# A02_DRV8316.net
KiCad netlist of a schematic drawn in Altium Designer
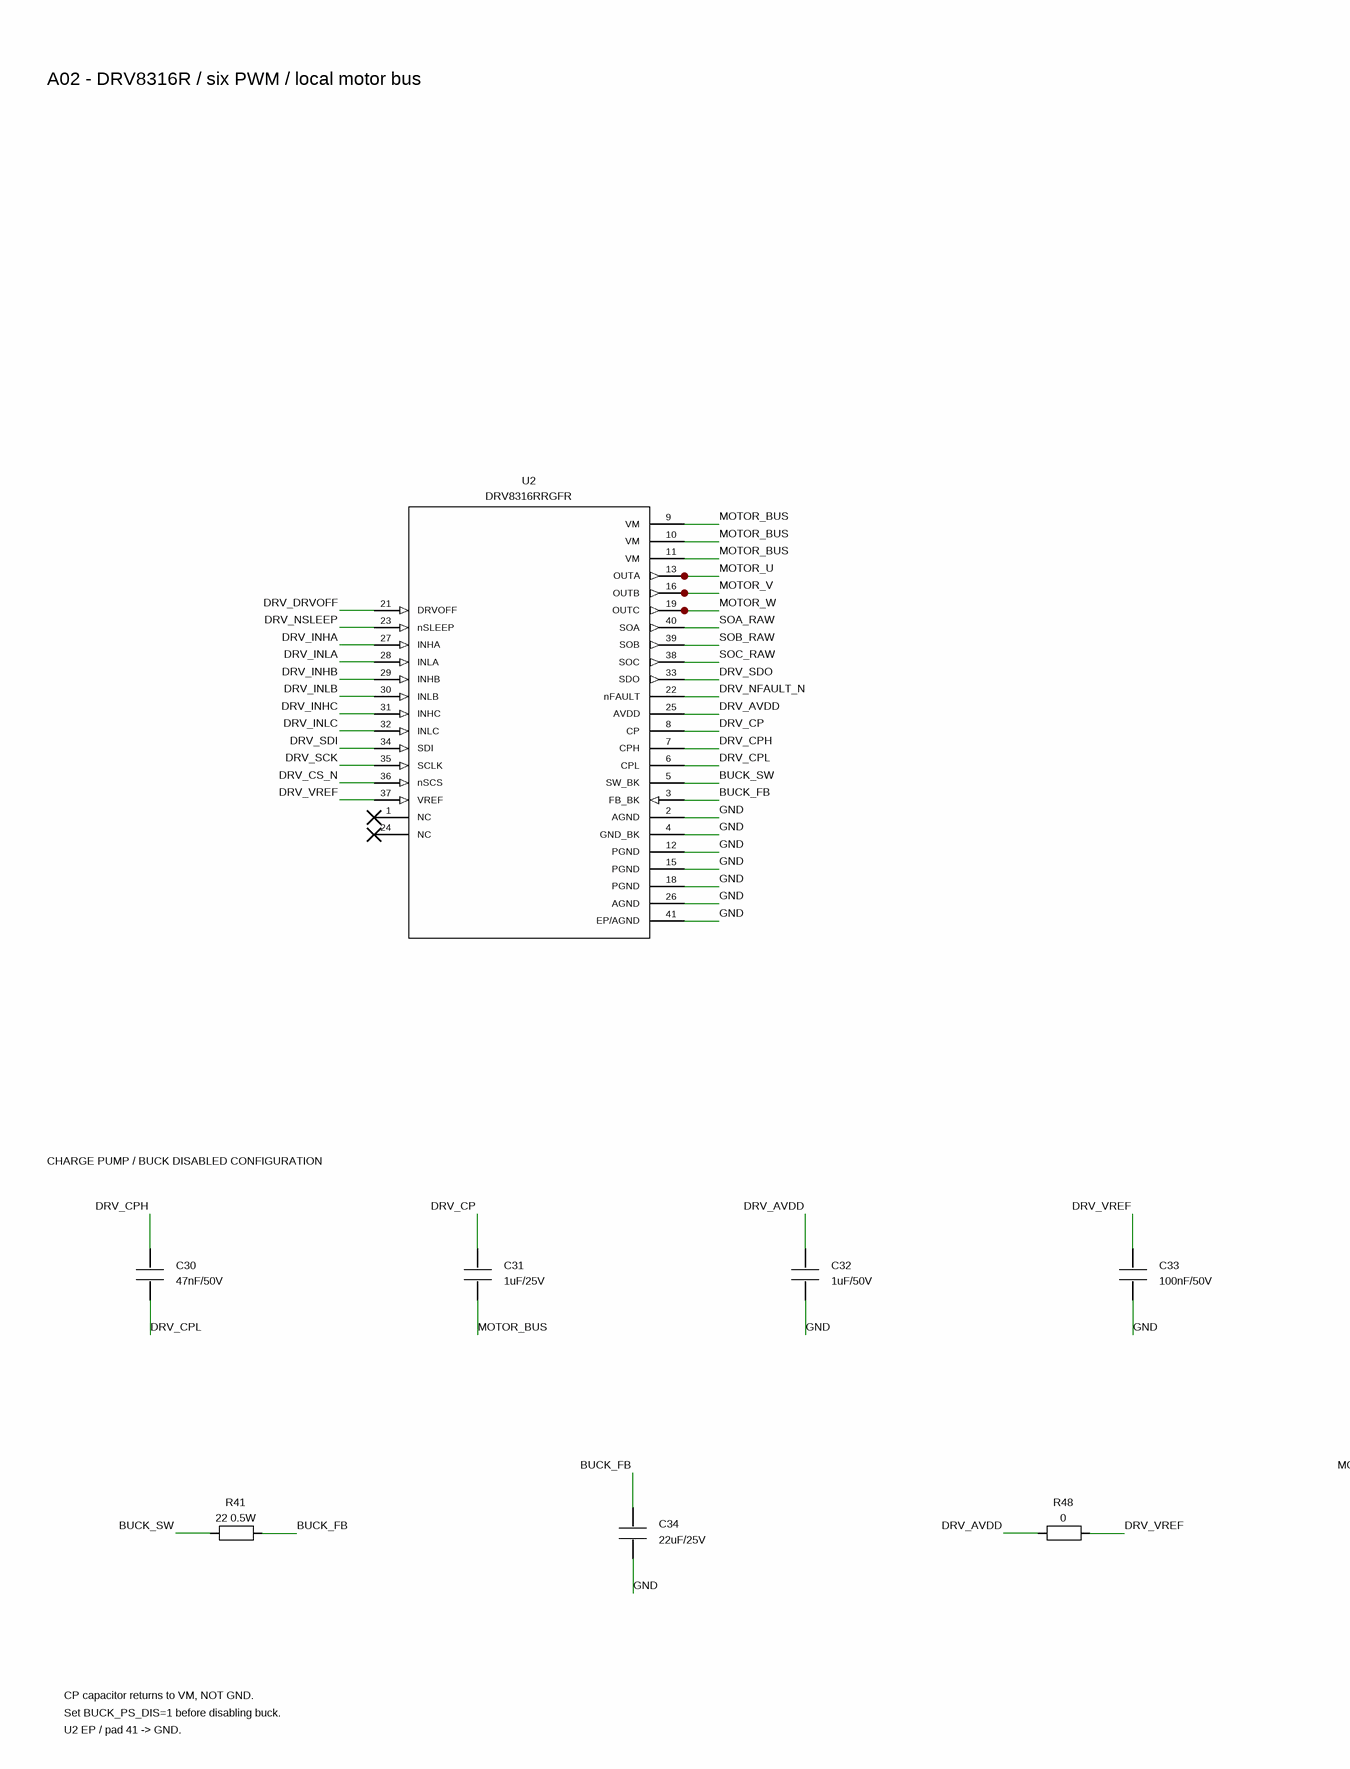
[diagram p0: A02_DRV8316.SchDoc, left]
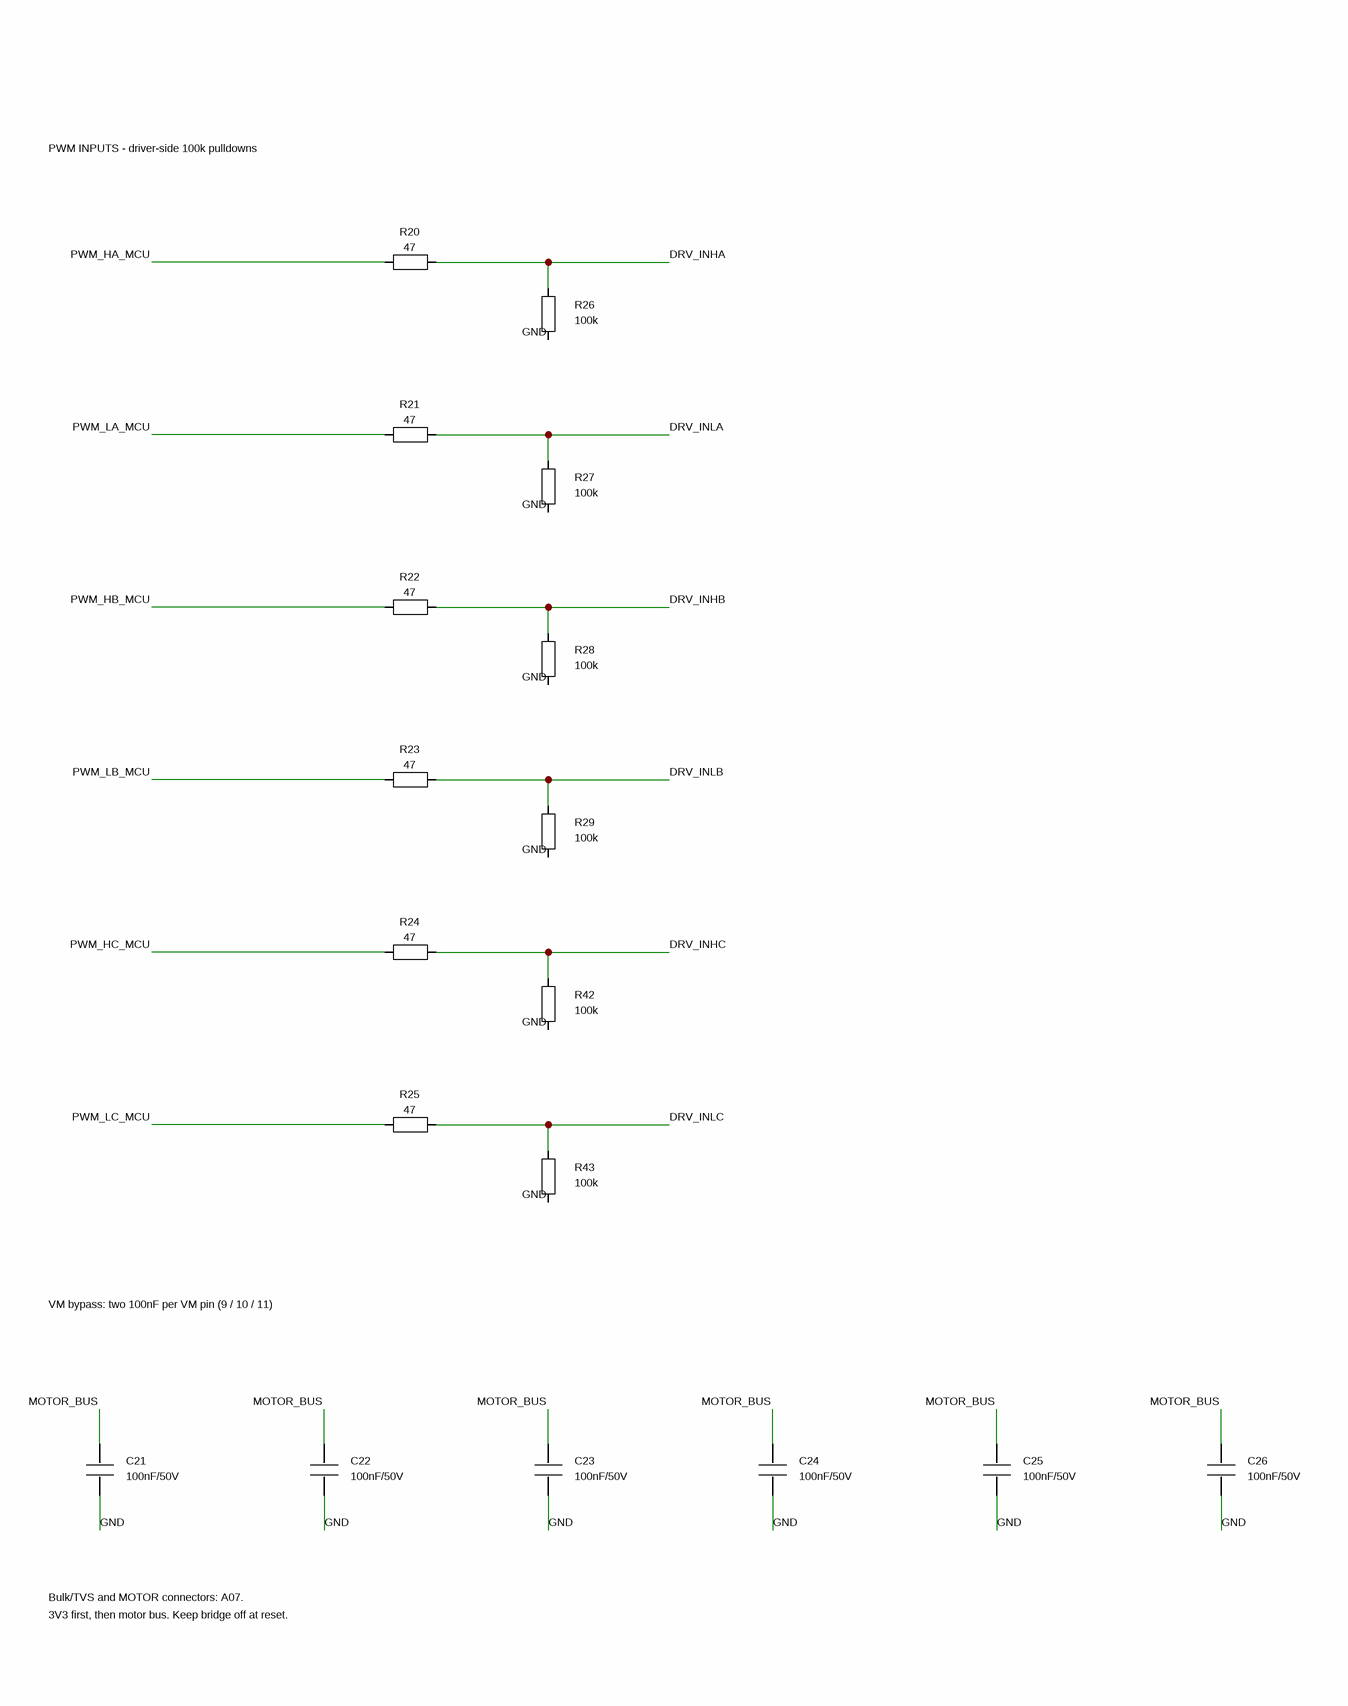
[diagram p1: A02_DRV8316.SchDoc, right]

(export (version "E")
  (design (tool "Eeschema 10.0.6"))
  (components
    (comp (ref "C21")
      (value "100nF/50V")
      (footprint "User_STM32F407_Ctrl:C0603_M")
      (description "电容")
      (fields (field (name "MPN") "CL10B104KB8NNNC"))
      (libsource (lib "altium-import") (part "root_0_C_"))
    )
    (comp (ref "C22")
      (value "100nF/50V")
      (footprint "User_STM32F407_Ctrl:C0603_M")
      (description "电容")
      (fields (field (name "MPN") "CL10B104KB8NNNC"))
      (libsource (lib "altium-import") (part "root_0_C_"))
    )
    (comp (ref "C23")
      (value "100nF/50V")
      (footprint "User_STM32F407_Ctrl:C0603_M")
      (description "电容")
      (fields (field (name "MPN") "CL10B104KB8NNNC"))
      (libsource (lib "altium-import") (part "root_0_C_"))
    )
    (comp (ref "C24")
      (value "100nF/50V")
      (footprint "User_STM32F407_Ctrl:C0603_M")
      (description "电容")
      (fields (field (name "MPN") "CL10B104KB8NNNC"))
      (libsource (lib "altium-import") (part "root_0_C_"))
    )
    (comp (ref "C25")
      (value "100nF/50V")
      (footprint "User_STM32F407_Ctrl:C0603_M")
      (description "电容")
      (fields (field (name "MPN") "CL10B104KB8NNNC"))
      (libsource (lib "altium-import") (part "root_0_C_"))
    )
    (comp (ref "C26")
      (value "100nF/50V")
      (footprint "User_STM32F407_Ctrl:C0603_M")
      (description "电容")
      (fields (field (name "MPN") "CL10B104KB8NNNC"))
      (libsource (lib "altium-import") (part "root_0_C_"))
    )
    (comp (ref "C30")
      (value "47nF/50V")
      (footprint "User_STM32F407_Ctrl:C0603_M")
      (description "电容")
      (fields (field (name "MPN") "CL10B473KB8NNNC"))
      (libsource (lib "altium-import") (part "root_0_C_"))
    )
    (comp (ref "C31")
      (value "1uF/25V")
      (footprint "User_STM32F407_Ctrl:C0603_M")
      (description "电容")
      (fields (field (name "MPN") "CL10A105KA8NNNC"))
      (libsource (lib "altium-import") (part "root_0_C_"))
    )
    (comp (ref "C32")
      (value "1uF/50V")
      (footprint "User_STM32F407_Ctrl:C0805_M")
      (description "电容")
      (fields (field (name "MPN") "CL21B105KBFNNNE"))
      (libsource (lib "altium-import") (part "root_0_C_"))
    )
    (comp (ref "C33")
      (value "100nF/50V")
      (footprint "User_STM32F407_Ctrl:C0603_M")
      (description "电容")
      (fields (field (name "MPN") "CL10B104KB8NNNC"))
      (libsource (lib "altium-import") (part "root_0_C_"))
    )
    (comp (ref "C34")
      (value "22uF/25V")
      (footprint "User_STM32F407_Ctrl:C0805_M")
      (description "电容")
      (fields (field (name "MPN") "CL21A226MAQNNNE"))
      (libsource (lib "altium-import") (part "root_0_C_"))
    )
    (comp (ref "R20")
      (value "47")
      (footprint "User_STM32F407_Ctrl:R0603_M")
      (description "电阻")
      (fields (field (name "MPN") "通用厚膜 47 1% 0.1 W"))
      (libsource (lib "altium-import") (part "root_1_R_"))
    )
    (comp (ref "R21")
      (value "47")
      (footprint "User_STM32F407_Ctrl:R0603_M")
      (description "电阻")
      (fields (field (name "MPN") "通用厚膜 47 1% 0.1 W"))
      (libsource (lib "altium-import") (part "root_1_R_"))
    )
    (comp (ref "R22")
      (value "47")
      (footprint "User_STM32F407_Ctrl:R0603_M")
      (description "电阻")
      (fields (field (name "MPN") "通用厚膜 47 1% 0.1 W"))
      (libsource (lib "altium-import") (part "root_1_R_"))
    )
    (comp (ref "R23")
      (value "47")
      (footprint "User_STM32F407_Ctrl:R0603_M")
      (description "电阻")
      (fields (field (name "MPN") "通用厚膜 47 1% 0.1 W"))
      (libsource (lib "altium-import") (part "root_1_R_"))
    )
    (comp (ref "R24")
      (value "47")
      (footprint "User_STM32F407_Ctrl:R0603_M")
      (description "电阻")
      (fields (field (name "MPN") "通用厚膜 47 1% 0.1 W"))
      (libsource (lib "altium-import") (part "root_1_R_"))
    )
    (comp (ref "R25")
      (value "47")
      (footprint "User_STM32F407_Ctrl:R0603_M")
      (description "电阻")
      (fields (field (name "MPN") "通用厚膜 47 1% 0.1 W"))
      (libsource (lib "altium-import") (part "root_1_R_"))
    )
    (comp (ref "R26")
      (value "100k")
      (footprint "User_STM32F407_Ctrl:R0603_M")
      (description "电阻")
      (fields (field (name "MPN") "通用厚膜 100k 1% 0.1 W"))
      (libsource (lib "altium-import") (part "root_0_R_"))
    )
    (comp (ref "R27")
      (value "100k")
      (footprint "User_STM32F407_Ctrl:R0603_M")
      (description "电阻")
      (fields (field (name "MPN") "通用厚膜 100k 1% 0.1 W"))
      (libsource (lib "altium-import") (part "root_0_R_"))
    )
    (comp (ref "R28")
      (value "100k")
      (footprint "User_STM32F407_Ctrl:R0603_M")
      (description "电阻")
      (fields (field (name "MPN") "通用厚膜 100k 1% 0.1 W"))
      (libsource (lib "altium-import") (part "root_0_R_"))
    )
    (comp (ref "R29")
      (value "100k")
      (footprint "User_STM32F407_Ctrl:R0603_M")
      (description "电阻")
      (fields (field (name "MPN") "通用厚膜 100k 1% 0.1 W"))
      (libsource (lib "altium-import") (part "root_0_R_"))
    )
    (comp (ref "R41")
      (value "22 0.5W")
      (footprint "User_SamacSys:RESC3116X65N")
      (description "电阻")
      (fields (field (name "MPN") "通用厚膜 22 1% 0.5 W"))
      (libsource (lib "altium-import") (part "root_1_R_"))
    )
    (comp (ref "R42")
      (value "100k")
      (footprint "User_STM32F407_Ctrl:R0603_M")
      (description "电阻")
      (fields (field (name "MPN") "通用厚膜 100k 1% 0.1 W"))
      (libsource (lib "altium-import") (part "root_0_R_"))
    )
    (comp (ref "R43")
      (value "100k")
      (footprint "User_STM32F407_Ctrl:R0603_M")
      (description "电阻")
      (fields (field (name "MPN") "通用厚膜 100k 1% 0.1 W"))
      (libsource (lib "altium-import") (part "root_0_R_"))
    )
    (comp (ref "R48")
      (value "0")
      (footprint "User_STM32F407_Ctrl:R0603_M")
      (description "电阻")
      (fields (field (name "MPN") "通用0Ω跳线 0.1 W"))
      (libsource (lib "altium-import") (part "root_1_R_"))
    )
    (comp (ref "U2")
      (value "DRV8316RRGFR")
      (footprint "User_LCSC:C5218861_VQFN-40_5x7")
      (description "三相集成驱动")
      (libsource (lib "altium-import") (part "root_0_DRV8316RRGFR_"))
    )
  )
  (nets
    (net (code "1") (name "/BUCK_FB") (class "Default")
      (node (ref "C34") (pin "1") (pintype "passive"))
      (node (ref "R41") (pin "2") (pintype "passive"))
      (node (ref "U2") (pin "3") (pinfunction "FB_BK_3") (pintype "input"))
    )
    (net (code "2") (name "/BUCK_SW") (class "Default")
      (node (ref "R41") (pin "1") (pintype "passive"))
      (node (ref "U2") (pin "5") (pinfunction "SW_BK_5") (pintype "passive"))
    )
    (net (code "3") (name "/DRV_AVDD") (class "Default")
      (node (ref "C32") (pin "1") (pintype "passive"))
      (node (ref "R48") (pin "1") (pintype "passive"))
      (node (ref "U2") (pin "25") (pinfunction "AVDD_25") (pintype "power_in"))
    )
    (net (code "4") (name "/DRV_CP") (class "Default")
      (node (ref "C31") (pin "1") (pintype "passive"))
      (node (ref "U2") (pin "8") (pinfunction "CP_8") (pintype "passive"))
    )
    (net (code "5") (name "/DRV_CPH") (class "Default")
      (node (ref "C30") (pin "1") (pintype "passive"))
      (node (ref "U2") (pin "7") (pinfunction "CPH_7") (pintype "passive"))
    )
    (net (code "6") (name "/DRV_CPL") (class "Default")
      (node (ref "C30") (pin "2") (pintype "passive"))
      (node (ref "U2") (pin "6") (pinfunction "CPL_6") (pintype "passive"))
    )
    (net (code "7") (name "/DRV_CS_N") (class "Default")
      (node (ref "U2") (pin "36") (pinfunction "nSCS_36") (pintype "input"))
    )
    (net (code "8") (name "/DRV_DRVOFF") (class "Default")
      (node (ref "U2") (pin "21") (pinfunction "DRVOFF_21") (pintype "input"))
    )
    (net (code "9") (name "/DRV_INHA") (class "Default")
      (node (ref "R20") (pin "2") (pintype "passive"))
      (node (ref "R26") (pin "1") (pintype "passive"))
      (node (ref "U2") (pin "27") (pinfunction "INHA_27") (pintype "input"))
    )
    (net (code "10") (name "/DRV_INHB") (class "Default")
      (node (ref "R22") (pin "2") (pintype "passive"))
      (node (ref "R28") (pin "1") (pintype "passive"))
      (node (ref "U2") (pin "29") (pinfunction "INHB_29") (pintype "input"))
    )
    (net (code "11") (name "/DRV_INHC") (class "Default")
      (node (ref "R24") (pin "2") (pintype "passive"))
      (node (ref "R42") (pin "1") (pintype "passive"))
      (node (ref "U2") (pin "31") (pinfunction "INHC_31") (pintype "input"))
    )
    (net (code "12") (name "/DRV_INLA") (class "Default")
      (node (ref "R21") (pin "2") (pintype "passive"))
      (node (ref "R27") (pin "1") (pintype "passive"))
      (node (ref "U2") (pin "28") (pinfunction "INLA_28") (pintype "input"))
    )
    (net (code "13") (name "/DRV_INLB") (class "Default")
      (node (ref "R23") (pin "2") (pintype "passive"))
      (node (ref "R29") (pin "1") (pintype "passive"))
      (node (ref "U2") (pin "30") (pinfunction "INLB_30") (pintype "input"))
    )
    (net (code "14") (name "/DRV_INLC") (class "Default")
      (node (ref "R25") (pin "2") (pintype "passive"))
      (node (ref "R43") (pin "1") (pintype "passive"))
      (node (ref "U2") (pin "32") (pinfunction "INLC_32") (pintype "input"))
    )
    (net (code "15") (name "/DRV_NFAULT_N") (class "Default")
      (node (ref "U2") (pin "22") (pinfunction "nFAULT_22") (pintype "open_collector"))
    )
    (net (code "16") (name "/DRV_NSLEEP") (class "Default")
      (node (ref "U2") (pin "23") (pinfunction "nSLEEP_23") (pintype "input"))
    )
    (net (code "17") (name "/DRV_SCK") (class "Default")
      (node (ref "U2") (pin "35") (pinfunction "SCLK_35") (pintype "input"))
    )
    (net (code "18") (name "/DRV_SDI") (class "Default")
      (node (ref "U2") (pin "34") (pinfunction "SDI_34") (pintype "input"))
    )
    (net (code "19") (name "/DRV_SDO") (class "Default")
      (node (ref "U2") (pin "33") (pinfunction "SDO_33") (pintype "output"))
    )
    (net (code "20") (name "/DRV_VREF") (class "Default")
      (node (ref "C33") (pin "1") (pintype "passive"))
      (node (ref "R48") (pin "2") (pintype "passive"))
      (node (ref "U2") (pin "37") (pinfunction "VREF_37") (pintype "input"))
    )
    (net (code "21") (name "/GND") (class "Default")
      (node (ref "C21") (pin "2") (pintype "passive"))
      (node (ref "C22") (pin "2") (pintype "passive"))
      (node (ref "C23") (pin "2") (pintype "passive"))
      (node (ref "C24") (pin "2") (pintype "passive"))
      (node (ref "C25") (pin "2") (pintype "passive"))
      (node (ref "C26") (pin "2") (pintype "passive"))
      (node (ref "C32") (pin "2") (pintype "passive"))
      (node (ref "C33") (pin "2") (pintype "passive"))
      (node (ref "C34") (pin "2") (pintype "passive"))
      (node (ref "R26") (pin "2") (pintype "passive"))
      (node (ref "R27") (pin "2") (pintype "passive"))
      (node (ref "R28") (pin "2") (pintype "passive"))
      (node (ref "R29") (pin "2") (pintype "passive"))
      (node (ref "R42") (pin "2") (pintype "passive"))
      (node (ref "R43") (pin "2") (pintype "passive"))
      (node (ref "U2") (pin "12") (pinfunction "PGND_12") (pintype "power_in"))
      (node (ref "U2") (pin "15") (pinfunction "PGND_15") (pintype "power_in"))
      (node (ref "U2") (pin "18") (pinfunction "PGND_18") (pintype "power_in"))
      (node (ref "U2") (pin "2") (pinfunction "AGND_2") (pintype "power_in"))
      (node (ref "U2") (pin "26") (pinfunction "AGND_26") (pintype "power_in"))
      (node (ref "U2") (pin "4") (pinfunction "GND_BK_4") (pintype "power_in"))
      (node (ref "U2") (pin "41") (pinfunction "EP/AGND_41") (pintype "power_in"))
    )
    (net (code "22") (name "/MOTOR_BUS") (class "Default")
      (node (ref "C21") (pin "1") (pintype "passive"))
      (node (ref "C22") (pin "1") (pintype "passive"))
      (node (ref "C23") (pin "1") (pintype "passive"))
      (node (ref "C24") (pin "1") (pintype "passive"))
      (node (ref "C25") (pin "1") (pintype "passive"))
      (node (ref "C26") (pin "1") (pintype "passive"))
      (node (ref "C31") (pin "2") (pintype "passive"))
      (node (ref "U2") (pin "10") (pinfunction "VM_10") (pintype "power_in"))
      (node (ref "U2") (pin "11") (pinfunction "VM_11") (pintype "power_in"))
      (node (ref "U2") (pin "9") (pinfunction "VM_9") (pintype "power_in"))
    )
    (net (code "23") (name "/MOTOR_U") (class "Default")
      (node (ref "U2") (pin "13") (pinfunction "OUTA_13") (pintype "output"))
      (node (ref "U2") (pin "14") (pinfunction "OUTA_14") (pintype "output"))
    )
    (net (code "24") (name "/MOTOR_V") (class "Default")
      (node (ref "U2") (pin "16") (pinfunction "OUTB_16") (pintype "output"))
      (node (ref "U2") (pin "17") (pinfunction "OUTB_17") (pintype "output"))
    )
    (net (code "25") (name "/MOTOR_W") (class "Default")
      (node (ref "U2") (pin "19") (pinfunction "OUTC_19") (pintype "output"))
      (node (ref "U2") (pin "20") (pinfunction "OUTC_20") (pintype "output"))
    )
    (net (code "26") (name "/PWM_HA_MCU") (class "Default") (node (ref "R20") (pin "1") (pintype "passive")))
    (net (code "27") (name "/PWM_HB_MCU") (class "Default") (node (ref "R22") (pin "1") (pintype "passive")))
    (net (code "28") (name "/PWM_HC_MCU") (class "Default") (node (ref "R24") (pin "1") (pintype "passive")))
    (net (code "29") (name "/PWM_LA_MCU") (class "Default") (node (ref "R21") (pin "1") (pintype "passive")))
    (net (code "30") (name "/PWM_LB_MCU") (class "Default") (node (ref "R23") (pin "1") (pintype "passive")))
    (net (code "31") (name "/PWM_LC_MCU") (class "Default") (node (ref "R25") (pin "1") (pintype "passive")))
    (net (code "32") (name "/SOA_RAW") (class "Default")
      (node (ref "U2") (pin "40") (pinfunction "SOA_40") (pintype "output"))
    )
    (net (code "33") (name "/SOB_RAW") (class "Default")
      (node (ref "U2") (pin "39") (pinfunction "SOB_39") (pintype "output"))
    )
    (net (code "34") (name "/SOC_RAW") (class "Default")
      (node (ref "U2") (pin "38") (pinfunction "SOC_38") (pintype "output"))
    )
    (net (code "35") (name "unconnected-(U2-NC-Pad1)") (class "Default")
      (node (ref "U2") (pin "1") (pinfunction "NC_1") (pintype "passive+no_connect"))
    )
    (net (code "36") (name "unconnected-(U2-NC-Pad24)") (class "Default")
      (node (ref "U2") (pin "24") (pinfunction "NC_24") (pintype "passive+no_connect"))
    )
  )
)
